# Sheet1.net
KiCad netlist of a schematic drawn in Altium Designer
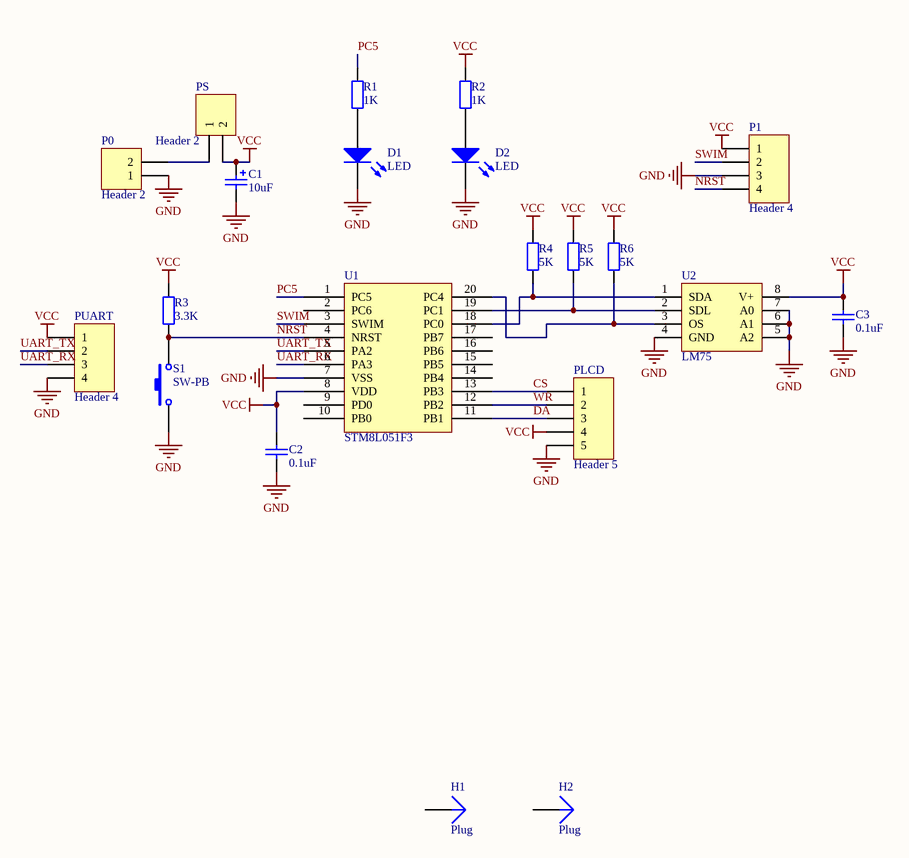
[diagram p0: Sheet1.SchDoc]

(export (version "E")
  (design (tool "Eeschema 10.0.6"))
  (components
    (comp (ref "C1")
      (value "10uF")
      (footprint "CapPol5_11")
      (description "Polarized Capacitor (Axial)")
      (fields (field (name "Comment") "Cap Pol2") (field (name "PUBLISHER") "Altium Limited"))
      (libsource (lib "Miscellaneous Devices") (part "Cap Pol2"))
    )
    (comp (ref "C2")
      (value "0.1uF")
      (footprint "0603_LMH")
      (description "Capacitor")
      (fields (field (name "Comment") "Cap") (field (name "PUBLISHER") "Altium Limited"))
      (libsource (lib "Miscellaneous Devices") (part "Cap"))
    )
    (comp (ref "C3")
      (value "0.1uF")
      (footprint "0603_LMH")
      (description "Capacitor")
      (fields (field (name "Comment") "Cap") (field (name "PUBLISHER") "Altium Limited"))
      (libsource (lib "Miscellaneous Devices") (part "Cap"))
    )
    (comp (ref "D1")
      (value "LED")
      (footprint "0603_LMH")
      (description "Typical INFRARED GaAs LED")
      (fields (field (name "PUBLISHER") "Altium Limited"))
      (libsource (lib "Miscellaneous Devices") (part "LED0"))
    )
    (comp (ref "D2")
      (value "LED")
      (footprint "0603_LMH")
      (description "Typical INFRARED GaAs LED")
      (fields (field (name "PUBLISHER") "Altium Limited"))
      (libsource (lib "Miscellaneous Devices") (part "LED0"))
    )
    (comp (ref "H1")
      (value "Plug")
      (footprint "OriginHole")
      (fields (field (name "PUBLISHER") "Altium Limited"))
      (libsource (lib "Miscellaneous Connectors") (part "Plug"))
    )
    (comp (ref "H2")
      (value "Plug")
      (footprint "OriginHole")
      (fields (field (name "PUBLISHER") "Altium Limited"))
      (libsource (lib "Miscellaneous Connectors") (part "Plug"))
    )
    (comp (ref "P0")
      (value "Header 2")
      (footprint "KF350-2P")
      (description "Header, 2-Pin")
      (fields (field (name "PUBLISHER") "Altium Limited"))
      (libsource (lib "") (part "Header 2_1"))
    )
    (comp (ref "P1")
      (value "Header 4")
      (footprint "HDR1X4")
      (description "Header, 4-Pin")
      (fields (field (name "PUBLISHER") "Altium Limited"))
      (libsource (lib "Miscellaneous Connectors") (part "Header 4"))
    )
    (comp (ref "PLCD")
      (value "Header 5")
      (footprint "HDR1X5")
      (description "Header, 5-Pin")
      (fields (field (name "PUBLISHER") "Altium Limited"))
      (libsource (lib "Miscellaneous Connectors") (part "Header 5"))
    )
    (comp (ref "PS")
      (value "Header 2")
      (footprint "HDR1X2")
      (description "Header, 2-Pin")
      (fields (field (name "PUBLISHER") "Altium Limited"))
      (libsource (lib "Miscellaneous Connectors") (part "Header 2"))
    )
    (comp (ref "PUART")
      (value "Header 4")
      (footprint "HDR1X4")
      (description "Header, 4-Pin")
      (fields (field (name "PUBLISHER") "Altium Limited"))
      (libsource (lib "Miscellaneous Connectors") (part "Header 4"))
    )
    (comp (ref "R1")
      (value "1K")
      (footprint "0805")
      (description "Resistor")
      (fields (field (name "Comment") "Res2") (field (name "PUBLISHER") "Altium Limited"))
      (libsource (lib "Miscellaneous Devices") (part "Res2"))
    )
    (comp (ref "R2")
      (value "1K")
      (footprint "0805")
      (description "Resistor")
      (fields (field (name "Comment") "Res2") (field (name "PUBLISHER") "Altium Limited"))
      (libsource (lib "Miscellaneous Devices") (part "Res2"))
    )
    (comp (ref "R3")
      (value "3.3K")
      (footprint "0805")
      (description "Resistor")
      (fields (field (name "Comment") "Res2") (field (name "PUBLISHER") "Altium Limited"))
      (libsource (lib "Miscellaneous Devices") (part "Res2"))
    )
    (comp (ref "R4")
      (value "5K")
      (footprint "0805")
      (description "Resistor")
      (fields (field (name "Comment") "Res2") (field (name "PUBLISHER") "Altium Limited"))
      (libsource (lib "Miscellaneous Devices") (part "Res2"))
    )
    (comp (ref "R5")
      (value "5K")
      (footprint "0805")
      (description "Resistor")
      (fields (field (name "Comment") "Res2") (field (name "PUBLISHER") "Altium Limited"))
      (libsource (lib "Miscellaneous Devices") (part "Res2"))
    )
    (comp (ref "R6")
      (value "5K")
      (footprint "0805")
      (description "Resistor")
      (fields (field (name "Comment") "Res2") (field (name "PUBLISHER") "Altium Limited"))
      (libsource (lib "Miscellaneous Devices") (part "Res2"))
    )
    (comp (ref "S1")
      (value "SW-PB")
      (footprint "SW-3X6X2.5")
      (description "Switch")
      (fields (field (name "PUBLISHER") "Altium Limited"))
      (libsource (lib "Miscellaneous Devices") (part "SW-PB"))
    )
    (comp (ref "U1")
      (value "STM8L051F3")
      (footprint "TSSOP20")
      (libsource (lib "MySchlib") (part "STM8L051F3"))
    )
    (comp (ref "U2") (value "LM75") (footprint "SOP8") (libsource (lib "MySchlib") (part "LM75")))
  )
  (nets
    (net (code "1") (name "/CS") (class "Default")
      (node (ref "PLCD") (pin "1") (pinfunction "1_1") (pintype "passive"))
      (node (ref "U1") (pin "13") (pinfunction "PB3_13") (pintype "passive"))
    )
    (net (code "2") (name "/DA") (class "Default")
      (node (ref "PLCD") (pin "3") (pinfunction "3_3") (pintype "passive"))
      (node (ref "U1") (pin "11") (pinfunction "PB1_11") (pintype "passive"))
    )
    (net (code "3") (name "/NRST") (class "Default")
      (node (ref "P1") (pin "4") (pinfunction "4_4") (pintype "passive"))
      (node (ref "R3") (pin "1") (pinfunction "1_1") (pintype "passive"))
      (node (ref "S1") (pin "2") (pinfunction "2_2") (pintype "passive"))
      (node (ref "U1") (pin "4") (pinfunction "NRST_4") (pintype "passive"))
    )
    (net (code "4") (name "/PC5") (class "Default")
      (node (ref "R1") (pin "2") (pinfunction "2_2") (pintype "passive"))
      (node (ref "U1") (pin "1") (pinfunction "PC5_1") (pintype "passive"))
    )
    (net (code "5") (name "/SWIM") (class "Default")
      (node (ref "P1") (pin "2") (pinfunction "2_2") (pintype "passive"))
      (node (ref "U1") (pin "3") (pinfunction "SWIM_3") (pintype "passive"))
    )
    (net (code "6") (name "/UART_RX") (class "Default")
      (node (ref "PUART") (pin "3") (pinfunction "3_3") (pintype "passive"))
      (node (ref "U1") (pin "6") (pinfunction "PA3_6") (pintype "passive"))
    )
    (net (code "7") (name "/UART_TX") (class "Default")
      (node (ref "PUART") (pin "2") (pinfunction "2_2") (pintype "passive"))
      (node (ref "U1") (pin "5") (pinfunction "PA2_5") (pintype "passive"))
    )
    (net (code "8") (name "/WR") (class "Default")
      (node (ref "PLCD") (pin "2") (pinfunction "2_2") (pintype "passive"))
      (node (ref "U1") (pin "12") (pinfunction "PB2_12") (pintype "passive"))
    )
    (net (code "9") (name "GND") (class "Default")
      (node (ref "C1") (pin "2") (pinfunction "2_2") (pintype "passive"))
      (node (ref "C2") (pin "1") (pinfunction "1_1") (pintype "passive"))
      (node (ref "C3") (pin "1") (pinfunction "1_1") (pintype "passive"))
      (node (ref "D1") (pin "2") (pinfunction "K_2") (pintype "passive"))
      (node (ref "D2") (pin "2") (pinfunction "K_2") (pintype "passive"))
      (node (ref "P0") (pin "1") (pinfunction "1_1") (pintype "passive"))
      (node (ref "P1") (pin "3") (pinfunction "3_3") (pintype "passive"))
      (node (ref "PLCD") (pin "5") (pinfunction "5_5") (pintype "passive"))
      (node (ref "PUART") (pin "4") (pinfunction "4_4") (pintype "passive"))
      (node (ref "S1") (pin "1") (pinfunction "1_1") (pintype "passive"))
      (node (ref "U1") (pin "7") (pinfunction "VSS_7") (pintype "passive"))
      (node (ref "U2") (pin "4") (pinfunction "GND_4") (pintype "passive"))
      (node (ref "U2") (pin "5") (pinfunction "A2_5") (pintype "passive"))
      (node (ref "U2") (pin "6") (pinfunction "A1_6") (pintype "passive"))
      (node (ref "U2") (pin "7") (pinfunction "A0_7") (pintype "passive"))
    )
    (net (code "10") (name "Net-(D1-A)") (class "Default")
      (node (ref "D1") (pin "1") (pinfunction "A_1") (pintype "passive"))
      (node (ref "R1") (pin "1") (pinfunction "1_1") (pintype "passive"))
    )
    (net (code "11") (name "Net-(D2-A)") (class "Default")
      (node (ref "D2") (pin "1") (pinfunction "A_1") (pintype "passive"))
      (node (ref "R2") (pin "1") (pinfunction "1_1") (pintype "passive"))
    )
    (net (code "12") (name "Net-(P0-Pad2)") (class "Default")
      (node (ref "P0") (pin "2") (pinfunction "2_2") (pintype "passive"))
      (node (ref "PS") (pin "1") (pinfunction "1_1") (pintype "passive"))
    )
    (net (code "13") (name "Net-(U1-PC0)") (class "Default")
      (node (ref "R4") (pin "1") (pinfunction "1_1") (pintype "passive"))
      (node (ref "U1") (pin "18") (pinfunction "PC0_18") (pintype "passive"))
      (node (ref "U2") (pin "1") (pinfunction "SDA_1") (pintype "passive"))
    )
    (net (code "14") (name "Net-(U1-PC1)") (class "Default")
      (node (ref "R5") (pin "1") (pinfunction "1_1") (pintype "passive"))
      (node (ref "U1") (pin "19") (pinfunction "PC1_19") (pintype "passive"))
      (node (ref "U2") (pin "2") (pinfunction "SDL_2") (pintype "passive"))
    )
    (net (code "15") (name "Net-(U1-PC4)") (class "Default")
      (node (ref "R6") (pin "1") (pinfunction "1_1") (pintype "passive"))
      (node (ref "U1") (pin "20") (pinfunction "PC4_20") (pintype "passive"))
      (node (ref "U2") (pin "3") (pinfunction "OS_3") (pintype "passive"))
    )
    (net (code "16") (name "VCC") (class "Default")
      (node (ref "C1") (pin "1") (pinfunction "1_1") (pintype "passive"))
      (node (ref "C2") (pin "2") (pinfunction "2_2") (pintype "passive"))
      (node (ref "C3") (pin "2") (pinfunction "2_2") (pintype "passive"))
      (node (ref "P1") (pin "1") (pinfunction "1_1") (pintype "passive"))
      (node (ref "PLCD") (pin "4") (pinfunction "4_4") (pintype "passive"))
      (node (ref "PS") (pin "2") (pinfunction "2_2") (pintype "passive"))
      (node (ref "PUART") (pin "1") (pinfunction "1_1") (pintype "passive"))
      (node (ref "R2") (pin "2") (pinfunction "2_2") (pintype "passive"))
      (node (ref "R3") (pin "2") (pinfunction "2_2") (pintype "passive"))
      (node (ref "R4") (pin "2") (pinfunction "2_2") (pintype "passive"))
      (node (ref "R5") (pin "2") (pinfunction "2_2") (pintype "passive"))
      (node (ref "R6") (pin "2") (pinfunction "2_2") (pintype "passive"))
      (node (ref "U1") (pin "8") (pinfunction "VDD_8") (pintype "passive"))
      (node (ref "U2") (pin "8") (pinfunction "V+_8") (pintype "passive"))
    )
    (net (code "17") (name "unconnected-(H1-Pad1)") (class "Default")
      (node (ref "H1") (pin "1") (pinfunction "1_1") (pintype "passive"))
    )
    (net (code "18") (name "unconnected-(H2-Pad1)") (class "Default")
      (node (ref "H2") (pin "1") (pinfunction "1_1") (pintype "passive"))
    )
    (net (code "19") (name "unconnected-(U1-PB0-Pad10)") (class "Default")
      (node (ref "U1") (pin "10") (pinfunction "PB0_10") (pintype "passive"))
    )
    (net (code "20") (name "unconnected-(U1-PB4-Pad14)") (class "Default")
      (node (ref "U1") (pin "14") (pinfunction "PB4_14") (pintype "passive"))
    )
    (net (code "21") (name "unconnected-(U1-PB5-Pad15)") (class "Default")
      (node (ref "U1") (pin "15") (pinfunction "PB5_15") (pintype "passive"))
    )
    (net (code "22") (name "unconnected-(U1-PB6-Pad16)") (class "Default")
      (node (ref "U1") (pin "16") (pinfunction "PB6_16") (pintype "passive"))
    )
    (net (code "23") (name "unconnected-(U1-PB7-Pad17)") (class "Default")
      (node (ref "U1") (pin "17") (pinfunction "PB7_17") (pintype "passive"))
    )
    (net (code "24") (name "unconnected-(U1-PC6-Pad2)") (class "Default")
      (node (ref "U1") (pin "2") (pinfunction "PC6_2") (pintype "passive"))
    )
    (net (code "25") (name "unconnected-(U1-PD0-Pad9)") (class "Default")
      (node (ref "U1") (pin "9") (pinfunction "PD0_9") (pintype "passive"))
    )
  )
)
